# Esp32_Shield.net
KiCad netlist of a schematic drawn in EAGLE
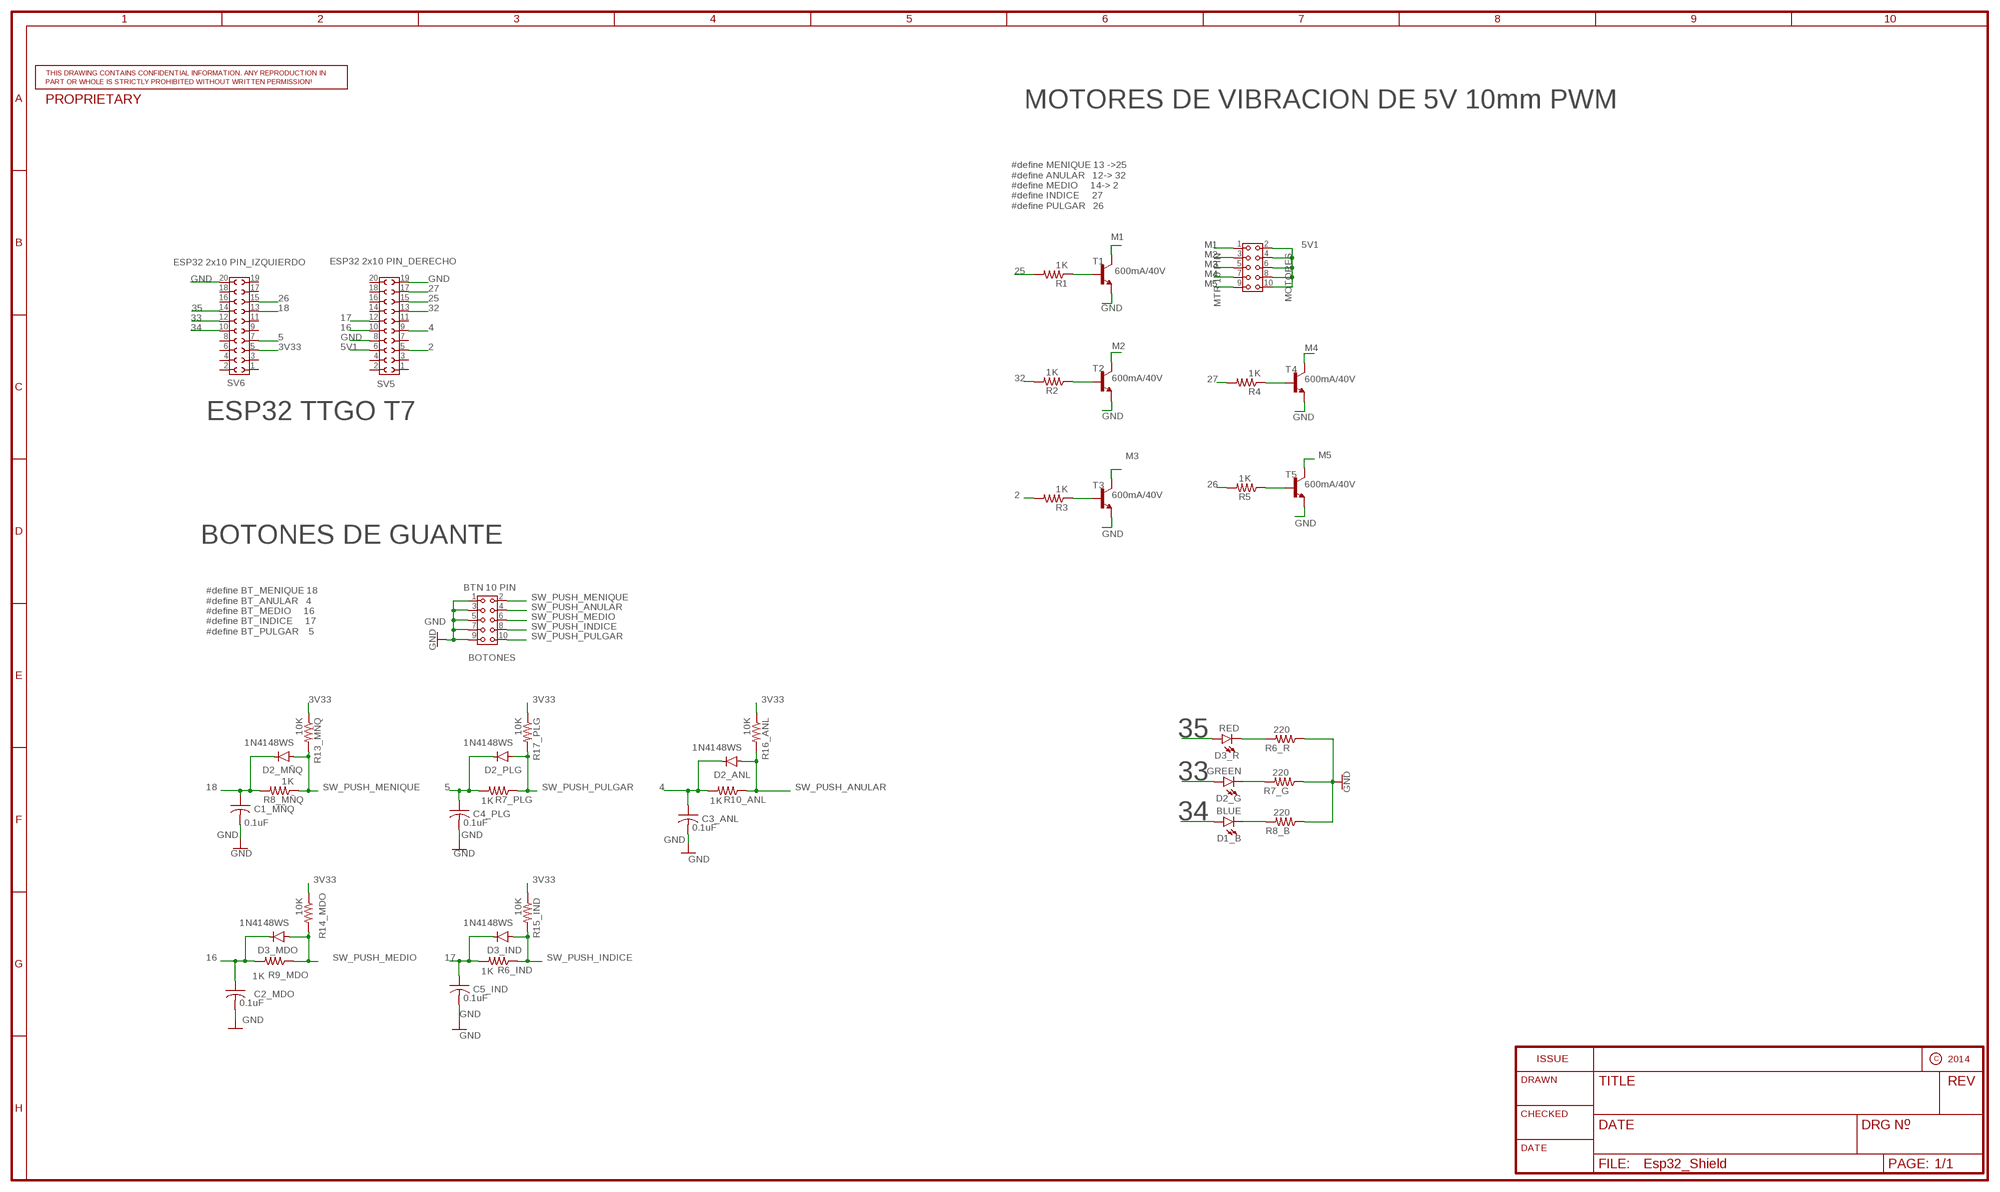
[diagram p0: schematic, sheet 1]

(export (version "E")
  (design (tool "Eeschema 10.0.6"))
  (components
    (comp (ref "BOTONES")
      (value "BTN 10 PIN")
      (footprint "eagle-import:61301021821")
      (libsource (lib "eagle-import") (part "6130XX21821_61301021821"))
    )
    (comp (ref "C1_MÑQ")
      (value "0.1uF")
      (footprint "eagle-import:C0805")
      (libsource (lib "eagle-import") (part "C-USC0805"))
    )
    (comp (ref "C2_MDO")
      (value "0.1uF")
      (footprint "eagle-import:C0805")
      (libsource (lib "eagle-import") (part "C-USC0805"))
    )
    (comp (ref "C3_ANL")
      (value "0.1uF")
      (footprint "eagle-import:C0805")
      (libsource (lib "eagle-import") (part "C-USC0805"))
    )
    (comp (ref "C4_PLG")
      (value "0.1uF")
      (footprint "eagle-import:C0805")
      (libsource (lib "eagle-import") (part "C-USC0805"))
    )
    (comp (ref "C5_IND")
      (value "0.1uF")
      (footprint "eagle-import:C0805")
      (libsource (lib "eagle-import") (part "C-USC0805"))
    )
    (comp (ref "D1_B")
      (value "BLUE")
      (footprint "eagle-import:LED-1206")
      (libsource (lib "eagle-import") (part "LED-BLUE1206"))
    )
    (comp (ref "D2_ANL")
      (value "1N4148WS")
      (footprint "eagle-import:SOD-323")
      (fields
        (field (name "DIGIKEY_PART_NUMBER") "1N4148WSFSTR-ND")
        (field (name "MANUFACTURER") "Diodes Incorporated")
        (field (name "CREATED_BY") "PCBLayout.com")
      )
      (libsource (lib "eagle-import") (part "1N4148WS"))
    )
    (comp (ref "D2_G")
      (value "GREEN")
      (footprint "eagle-import:LED-1206")
      (libsource (lib "eagle-import") (part "LED-GREEN1206"))
    )
    (comp (ref "D2_MÑQ")
      (value "1N4148WS")
      (footprint "eagle-import:SOD-323")
      (fields
        (field (name "DIGIKEY_PART_NUMBER") "1N4148WSFSTR-ND")
        (field (name "MANUFACTURER") "Diodes Incorporated")
        (field (name "CREATED_BY") "PCBLayout.com")
      )
      (libsource (lib "eagle-import") (part "1N4148WS"))
    )
    (comp (ref "D2_PLG")
      (value "1N4148WS")
      (footprint "eagle-import:SOD-323")
      (fields
        (field (name "DIGIKEY_PART_NUMBER") "1N4148WSFSTR-ND")
        (field (name "MANUFACTURER") "Diodes Incorporated")
        (field (name "CREATED_BY") "PCBLayout.com")
      )
      (libsource (lib "eagle-import") (part "1N4148WS"))
    )
    (comp (ref "D3_IND")
      (value "1N4148WS")
      (footprint "eagle-import:SOD-323")
      (fields
        (field (name "DIGIKEY_PART_NUMBER") "1N4148WSFSTR-ND")
        (field (name "MANUFACTURER") "Diodes Incorporated")
        (field (name "CREATED_BY") "PCBLayout.com")
      )
      (libsource (lib "eagle-import") (part "1N4148WS"))
    )
    (comp (ref "D3_MDO")
      (value "1N4148WS")
      (footprint "eagle-import:SOD-323")
      (fields
        (field (name "DIGIKEY_PART_NUMBER") "1N4148WSFSTR-ND")
        (field (name "MANUFACTURER") "Diodes Incorporated")
        (field (name "CREATED_BY") "PCBLayout.com")
      )
      (libsource (lib "eagle-import") (part "1N4148WS"))
    )
    (comp (ref "D3_R")
      (value "RED")
      (footprint "eagle-import:LED-1206")
      (libsource (lib "eagle-import") (part "LED-RED1206"))
    )
    (comp (ref "MOTORES")
      (value "MTR 10 PIN")
      (footprint "eagle-import:61301021821")
      (libsource (lib "eagle-import") (part "6130XX21821_61301021821"))
    )
    (comp (ref "R1")
      (value "1K")
      (footprint "eagle-import:R0805")
      (libsource (lib "eagle-import") (part "R-US_R0805"))
    )
    (comp (ref "R2")
      (value "1K")
      (footprint "eagle-import:R0805")
      (libsource (lib "eagle-import") (part "R-US_R0805"))
    )
    (comp (ref "R3")
      (value "1K")
      (footprint "eagle-import:R0805")
      (libsource (lib "eagle-import") (part "R-US_R0805"))
    )
    (comp (ref "R4")
      (value "1K")
      (footprint "eagle-import:R0805")
      (libsource (lib "eagle-import") (part "R-US_R0805"))
    )
    (comp (ref "R5")
      (value "1K")
      (footprint "eagle-import:R0805")
      (libsource (lib "eagle-import") (part "R-US_R0805"))
    )
    (comp (ref "R6_IND")
      (value "1K")
      (footprint "eagle-import:R0805")
      (libsource (lib "eagle-import") (part "R-US_R0805"))
    )
    (comp (ref "R6_R")
      (value "220")
      (footprint "eagle-import:R0805")
      (libsource (lib "eagle-import") (part "R-US_R0805"))
    )
    (comp (ref "R7_G")
      (value "220")
      (footprint "eagle-import:R0805")
      (libsource (lib "eagle-import") (part "R-US_R0805"))
    )
    (comp (ref "R7_PLG")
      (value "1K")
      (footprint "eagle-import:R0805")
      (libsource (lib "eagle-import") (part "R-US_R0805"))
    )
    (comp (ref "R8_B")
      (value "220")
      (footprint "eagle-import:R0805")
      (libsource (lib "eagle-import") (part "R-US_R0805"))
    )
    (comp (ref "R8_MÑQ")
      (value "1K")
      (footprint "eagle-import:R0805")
      (libsource (lib "eagle-import") (part "R-US_R0805"))
    )
    (comp (ref "R9_MDO")
      (value "1K")
      (footprint "eagle-import:R0805")
      (libsource (lib "eagle-import") (part "R-US_R0805"))
    )
    (comp (ref "R10_ANL")
      (value "1K")
      (footprint "eagle-import:R0805")
      (libsource (lib "eagle-import") (part "R-US_R0805"))
    )
    (comp (ref "R13_MÑQ")
      (value "10K")
      (footprint "eagle-import:R0805")
      (libsource (lib "eagle-import") (part "R-US_R0805"))
    )
    (comp (ref "R14_MDO")
      (value "10K")
      (footprint "eagle-import:R0805")
      (libsource (lib "eagle-import") (part "R-US_R0805"))
    )
    (comp (ref "R15_IND")
      (value "10K")
      (footprint "eagle-import:R0805")
      (libsource (lib "eagle-import") (part "R-US_R0805"))
    )
    (comp (ref "R16_ANL")
      (value "10K")
      (footprint "eagle-import:R0805")
      (libsource (lib "eagle-import") (part "R-US_R0805"))
    )
    (comp (ref "R17_PLG")
      (value "10K")
      (footprint "eagle-import:R0805")
      (libsource (lib "eagle-import") (part "R-US_R0805"))
    )
    (comp (ref "SV5")
      (value "ESP32 2x10 PIN_DERECHO")
      (footprint "eagle-import:61302021821")
      (libsource (lib "eagle-import") (part "6130XX21821_61302021821"))
    )
    (comp (ref "SV6")
      (value "ESP32 2x10 PIN_IZQUIERDO")
      (footprint "eagle-import:61302021821")
      (libsource (lib "eagle-import") (part "6130XX21821_61302021821"))
    )
    (comp (ref "T1")
      (value "600mA/40V")
      (footprint "eagle-import:SOT23-3")
      (libsource (lib "eagle-import") (part "TRANS_NPN-MMBT2222AL"))
    )
    (comp (ref "T2")
      (value "600mA/40V")
      (footprint "eagle-import:SOT23-3")
      (libsource (lib "eagle-import") (part "TRANS_NPN-MMBT2222AL"))
    )
    (comp (ref "T3")
      (value "600mA/40V")
      (footprint "eagle-import:SOT23-3")
      (libsource (lib "eagle-import") (part "TRANS_NPN-MMBT2222AL"))
    )
    (comp (ref "T4")
      (value "600mA/40V")
      (footprint "eagle-import:SOT23-3")
      (libsource (lib "eagle-import") (part "TRANS_NPN-MMBT2222AL"))
    )
    (comp (ref "T5")
      (value "600mA/40V")
      (footprint "eagle-import:SOT23-3")
      (libsource (lib "eagle-import") (part "TRANS_NPN-MMBT2222AL"))
    )
  )
  (nets
    (net (code "1") (name "/2") (class "Default")
      (node (ref "R3") (pin "2") (pinfunction "2_2") (pintype "passive"))
      (node (ref "SV5") (pin "5") (pinfunction "5_5") (pintype "passive"))
    )
    (net (code "2") (name "/3V33") (class "Default")
      (node (ref "R13_MÑQ") (pin "1") (pinfunction "1_1") (pintype "passive"))
      (node (ref "R14_MDO") (pin "1") (pinfunction "1_1") (pintype "passive"))
      (node (ref "R15_IND") (pin "1") (pinfunction "1_1") (pintype "passive"))
      (node (ref "R16_ANL") (pin "1") (pinfunction "1_1") (pintype "passive"))
      (node (ref "R17_PLG") (pin "1") (pinfunction "1_1") (pintype "passive"))
      (node (ref "SV6") (pin "5") (pinfunction "5_5") (pintype "passive"))
    )
    (net (code "3") (name "/4") (class "Default")
      (node (ref "C3_ANL") (pin "1") (pinfunction "1_1") (pintype "passive"))
      (node (ref "D2_ANL") (pin "C") (pinfunction "C_C") (pintype "passive"))
      (node (ref "R10_ANL") (pin "2") (pinfunction "2_2") (pintype "passive"))
      (node (ref "SV5") (pin "9") (pinfunction "9_9") (pintype "passive"))
    )
    (net (code "4") (name "/5") (class "Default")
      (node (ref "C4_PLG") (pin "1") (pinfunction "1_1") (pintype "passive"))
      (node (ref "D2_PLG") (pin "C") (pinfunction "C_C") (pintype "passive"))
      (node (ref "R7_PLG") (pin "2") (pinfunction "2_2") (pintype "passive"))
      (node (ref "SV6") (pin "7") (pinfunction "7_7") (pintype "passive"))
    )
    (net (code "5") (name "/5V1") (class "Default")
      (node (ref "MOTORES") (pin "10") (pinfunction "10_10") (pintype "passive"))
      (node (ref "MOTORES") (pin "2") (pinfunction "2_2") (pintype "passive"))
      (node (ref "MOTORES") (pin "4") (pinfunction "4_4") (pintype "passive"))
      (node (ref "MOTORES") (pin "6") (pinfunction "6_6") (pintype "passive"))
      (node (ref "MOTORES") (pin "8") (pinfunction "8_8") (pintype "passive"))
      (node (ref "SV5") (pin "6") (pinfunction "6_6") (pintype "passive"))
    )
    (net (code "6") (name "/16") (class "Default")
      (node (ref "C2_MDO") (pin "1") (pinfunction "1_1") (pintype "passive"))
      (node (ref "D3_MDO") (pin "C") (pinfunction "C_C") (pintype "passive"))
      (node (ref "R9_MDO") (pin "2") (pinfunction "2_2") (pintype "passive"))
      (node (ref "SV5") (pin "10") (pinfunction "10_10") (pintype "passive"))
    )
    (net (code "7") (name "/17") (class "Default")
      (node (ref "C5_IND") (pin "1") (pinfunction "1_1") (pintype "passive"))
      (node (ref "D3_IND") (pin "C") (pinfunction "C_C") (pintype "passive"))
      (node (ref "R6_IND") (pin "2") (pinfunction "2_2") (pintype "passive"))
      (node (ref "SV5") (pin "12") (pinfunction "12_12") (pintype "passive"))
    )
    (net (code "8") (name "/18") (class "Default")
      (node (ref "C1_MÑQ") (pin "1") (pinfunction "1_1") (pintype "passive"))
      (node (ref "D2_MÑQ") (pin "C") (pinfunction "C_C") (pintype "passive"))
      (node (ref "R8_MÑQ") (pin "2") (pinfunction "2_2") (pintype "passive"))
      (node (ref "SV6") (pin "13") (pinfunction "13_13") (pintype "passive"))
    )
    (net (code "9") (name "/25") (class "Default")
      (node (ref "R1") (pin "2") (pinfunction "2_2") (pintype "passive"))
      (node (ref "SV5") (pin "15") (pinfunction "15_15") (pintype "passive"))
    )
    (net (code "10") (name "/26") (class "Default")
      (node (ref "R5") (pin "2") (pinfunction "2_2") (pintype "passive"))
      (node (ref "SV6") (pin "15") (pinfunction "15_15") (pintype "passive"))
    )
    (net (code "11") (name "/27") (class "Default")
      (node (ref "R4") (pin "2") (pinfunction "2_2") (pintype "passive"))
      (node (ref "SV5") (pin "17") (pinfunction "17_17") (pintype "passive"))
    )
    (net (code "12") (name "/32") (class "Default")
      (node (ref "R2") (pin "2") (pinfunction "2_2") (pintype "passive"))
      (node (ref "SV5") (pin "13") (pinfunction "13_13") (pintype "passive"))
    )
    (net (code "13") (name "/33") (class "Default")
      (node (ref "D2_G") (pin "A") (pinfunction "A_A") (pintype "passive"))
      (node (ref "SV6") (pin "12") (pinfunction "12_12") (pintype "passive"))
    )
    (net (code "14") (name "/34") (class "Default")
      (node (ref "D1_B") (pin "A") (pinfunction "A_A") (pintype "passive"))
      (node (ref "SV6") (pin "10") (pinfunction "10_10") (pintype "passive"))
    )
    (net (code "15") (name "/35") (class "Default")
      (node (ref "D3_R") (pin "A") (pinfunction "A_A") (pintype "passive"))
      (node (ref "SV6") (pin "14") (pinfunction "14_14") (pintype "passive"))
    )
    (net (code "16") (name "/M1") (class "Default")
      (node (ref "MOTORES") (pin "1") (pinfunction "1_1") (pintype "passive"))
      (node (ref "T1") (pin "3") (pinfunction "C_3") (pintype "passive"))
    )
    (net (code "17") (name "/M2") (class "Default")
      (node (ref "MOTORES") (pin "3") (pinfunction "3_3") (pintype "passive"))
      (node (ref "T2") (pin "3") (pinfunction "C_3") (pintype "passive"))
    )
    (net (code "18") (name "/M3") (class "Default")
      (node (ref "MOTORES") (pin "5") (pinfunction "5_5") (pintype "passive"))
      (node (ref "T3") (pin "3") (pinfunction "C_3") (pintype "passive"))
    )
    (net (code "19") (name "/M4") (class "Default")
      (node (ref "MOTORES") (pin "7") (pinfunction "7_7") (pintype "passive"))
      (node (ref "T4") (pin "3") (pinfunction "C_3") (pintype "passive"))
    )
    (net (code "20") (name "/M5") (class "Default")
      (node (ref "MOTORES") (pin "9") (pinfunction "9_9") (pintype "passive"))
      (node (ref "T5") (pin "3") (pinfunction "C_3") (pintype "passive"))
    )
    (net (code "21") (name "/SW_PUSH_ANULAR") (class "Default")
      (node (ref "BOTONES") (pin "4") (pinfunction "4_4") (pintype "passive"))
      (node (ref "D2_ANL") (pin "A") (pinfunction "A_A") (pintype "passive"))
      (node (ref "R10_ANL") (pin "1") (pinfunction "1_1") (pintype "passive"))
      (node (ref "R16_ANL") (pin "2") (pinfunction "2_2") (pintype "passive"))
    )
    (net (code "22") (name "/SW_PUSH_INDICE") (class "Default")
      (node (ref "BOTONES") (pin "8") (pinfunction "8_8") (pintype "passive"))
      (node (ref "D3_IND") (pin "A") (pinfunction "A_A") (pintype "passive"))
      (node (ref "R15_IND") (pin "2") (pinfunction "2_2") (pintype "passive"))
      (node (ref "R6_IND") (pin "1") (pinfunction "1_1") (pintype "passive"))
    )
    (net (code "23") (name "/SW_PUSH_MEDIO") (class "Default")
      (node (ref "BOTONES") (pin "6") (pinfunction "6_6") (pintype "passive"))
      (node (ref "D3_MDO") (pin "A") (pinfunction "A_A") (pintype "passive"))
      (node (ref "R14_MDO") (pin "2") (pinfunction "2_2") (pintype "passive"))
      (node (ref "R9_MDO") (pin "1") (pinfunction "1_1") (pintype "passive"))
    )
    (net (code "24") (name "/SW_PUSH_MENIQUE") (class "Default")
      (node (ref "BOTONES") (pin "2") (pinfunction "2_2") (pintype "passive"))
      (node (ref "D2_MÑQ") (pin "A") (pinfunction "A_A") (pintype "passive"))
      (node (ref "R13_MÑQ") (pin "2") (pinfunction "2_2") (pintype "passive"))
      (node (ref "R8_MÑQ") (pin "1") (pinfunction "1_1") (pintype "passive"))
    )
    (net (code "25") (name "/SW_PUSH_PULGAR") (class "Default")
      (node (ref "BOTONES") (pin "10") (pinfunction "10_10") (pintype "passive"))
      (node (ref "D2_PLG") (pin "A") (pinfunction "A_A") (pintype "passive"))
      (node (ref "R17_PLG") (pin "2") (pinfunction "2_2") (pintype "passive"))
      (node (ref "R7_PLG") (pin "1") (pinfunction "1_1") (pintype "passive"))
    )
    (net (code "26") (name "GND") (class "Default")
      (node (ref "BOTONES") (pin "1") (pinfunction "1_1") (pintype "passive"))
      (node (ref "BOTONES") (pin "3") (pinfunction "3_3") (pintype "passive"))
      (node (ref "BOTONES") (pin "5") (pinfunction "5_5") (pintype "passive"))
      (node (ref "BOTONES") (pin "7") (pinfunction "7_7") (pintype "passive"))
      (node (ref "BOTONES") (pin "9") (pinfunction "9_9") (pintype "passive"))
      (node (ref "C1_MÑQ") (pin "2") (pinfunction "2_2") (pintype "passive"))
      (node (ref "C2_MDO") (pin "2") (pinfunction "2_2") (pintype "passive"))
      (node (ref "C3_ANL") (pin "2") (pinfunction "2_2") (pintype "passive"))
      (node (ref "C4_PLG") (pin "2") (pinfunction "2_2") (pintype "passive"))
      (node (ref "C5_IND") (pin "2") (pinfunction "2_2") (pintype "passive"))
      (node (ref "R6_R") (pin "1") (pinfunction "1_1") (pintype "passive"))
      (node (ref "R7_G") (pin "1") (pinfunction "1_1") (pintype "passive"))
      (node (ref "R8_B") (pin "1") (pinfunction "1_1") (pintype "passive"))
      (node (ref "SV5") (pin "19") (pinfunction "19_19") (pintype "passive"))
      (node (ref "SV5") (pin "8") (pinfunction "8_8") (pintype "passive"))
      (node (ref "SV6") (pin "20") (pinfunction "20_20") (pintype "passive"))
      (node (ref "T1") (pin "2") (pinfunction "E_2") (pintype "passive"))
      (node (ref "T2") (pin "2") (pinfunction "E_2") (pintype "passive"))
      (node (ref "T3") (pin "2") (pinfunction "E_2") (pintype "passive"))
      (node (ref "T4") (pin "2") (pinfunction "E_2") (pintype "passive"))
      (node (ref "T5") (pin "2") (pinfunction "E_2") (pintype "passive"))
    )
    (net (code "27") (name "Net-(D1_B-PadC)") (class "Default")
      (node (ref "D1_B") (pin "C") (pinfunction "C_C") (pintype "passive"))
      (node (ref "R8_B") (pin "2") (pinfunction "2_2") (pintype "passive"))
    )
    (net (code "28") (name "Net-(D2_G-PadC)") (class "Default")
      (node (ref "D2_G") (pin "C") (pinfunction "C_C") (pintype "passive"))
      (node (ref "R7_G") (pin "2") (pinfunction "2_2") (pintype "passive"))
    )
    (net (code "29") (name "Net-(D3_R-PadC)") (class "Default")
      (node (ref "D3_R") (pin "C") (pinfunction "C_C") (pintype "passive"))
      (node (ref "R6_R") (pin "2") (pinfunction "2_2") (pintype "passive"))
    )
    (net (code "30") (name "Net-(T1-B)") (class "Default")
      (node (ref "R1") (pin "1") (pinfunction "1_1") (pintype "passive"))
      (node (ref "T1") (pin "1") (pinfunction "B_1") (pintype "passive"))
    )
    (net (code "31") (name "Net-(T2-B)") (class "Default")
      (node (ref "R2") (pin "1") (pinfunction "1_1") (pintype "passive"))
      (node (ref "T2") (pin "1") (pinfunction "B_1") (pintype "passive"))
    )
    (net (code "32") (name "Net-(T3-B)") (class "Default")
      (node (ref "R3") (pin "1") (pinfunction "1_1") (pintype "passive"))
      (node (ref "T3") (pin "1") (pinfunction "B_1") (pintype "passive"))
    )
    (net (code "33") (name "Net-(T4-B)") (class "Default")
      (node (ref "R4") (pin "1") (pinfunction "1_1") (pintype "passive"))
      (node (ref "T4") (pin "1") (pinfunction "B_1") (pintype "passive"))
    )
    (net (code "34") (name "Net-(T5-B)") (class "Default")
      (node (ref "R5") (pin "1") (pinfunction "1_1") (pintype "passive"))
      (node (ref "T5") (pin "1") (pinfunction "B_1") (pintype "passive"))
    )
    (net (code "35") (name "unconnected-(SV5-Pad1)") (class "Default")
      (node (ref "SV5") (pin "1") (pinfunction "1_1") (pintype "passive"))
    )
    (net (code "36") (name "unconnected-(SV5-Pad2)") (class "Default")
      (node (ref "SV5") (pin "2") (pinfunction "2_2") (pintype "passive"))
    )
    (net (code "37") (name "unconnected-(SV5-Pad3)") (class "Default")
      (node (ref "SV5") (pin "3") (pinfunction "3_3") (pintype "passive"))
    )
    (net (code "38") (name "unconnected-(SV5-Pad4)") (class "Default")
      (node (ref "SV5") (pin "4") (pinfunction "4_4") (pintype "passive"))
    )
    (net (code "39") (name "unconnected-(SV5-Pad7)") (class "Default")
      (node (ref "SV5") (pin "7") (pinfunction "7_7") (pintype "passive"))
    )
    (net (code "40") (name "unconnected-(SV5-Pad11)") (class "Default")
      (node (ref "SV5") (pin "11") (pinfunction "11_11") (pintype "passive"))
    )
    (net (code "41") (name "unconnected-(SV5-Pad14)") (class "Default")
      (node (ref "SV5") (pin "14") (pinfunction "14_14") (pintype "passive"))
    )
    (net (code "42") (name "unconnected-(SV5-Pad16)") (class "Default")
      (node (ref "SV5") (pin "16") (pinfunction "16_16") (pintype "passive"))
    )
    (net (code "43") (name "unconnected-(SV5-Pad18)") (class "Default")
      (node (ref "SV5") (pin "18") (pinfunction "18_18") (pintype "passive"))
    )
    (net (code "44") (name "unconnected-(SV5-Pad20)") (class "Default")
      (node (ref "SV5") (pin "20") (pinfunction "20_20") (pintype "passive"))
    )
    (net (code "45") (name "unconnected-(SV6-Pad1)") (class "Default")
      (node (ref "SV6") (pin "1") (pinfunction "1_1") (pintype "passive"))
    )
    (net (code "46") (name "unconnected-(SV6-Pad2)") (class "Default")
      (node (ref "SV6") (pin "2") (pinfunction "2_2") (pintype "passive"))
    )
    (net (code "47") (name "unconnected-(SV6-Pad3)") (class "Default")
      (node (ref "SV6") (pin "3") (pinfunction "3_3") (pintype "passive"))
    )
    (net (code "48") (name "unconnected-(SV6-Pad4)") (class "Default")
      (node (ref "SV6") (pin "4") (pinfunction "4_4") (pintype "passive"))
    )
    (net (code "49") (name "unconnected-(SV6-Pad6)") (class "Default")
      (node (ref "SV6") (pin "6") (pinfunction "6_6") (pintype "passive"))
    )
    (net (code "50") (name "unconnected-(SV6-Pad8)") (class "Default")
      (node (ref "SV6") (pin "8") (pinfunction "8_8") (pintype "passive"))
    )
    (net (code "51") (name "unconnected-(SV6-Pad9)") (class "Default")
      (node (ref "SV6") (pin "9") (pinfunction "9_9") (pintype "passive"))
    )
    (net (code "52") (name "unconnected-(SV6-Pad11)") (class "Default")
      (node (ref "SV6") (pin "11") (pinfunction "11_11") (pintype "passive"))
    )
    (net (code "53") (name "unconnected-(SV6-Pad16)") (class "Default")
      (node (ref "SV6") (pin "16") (pinfunction "16_16") (pintype "passive"))
    )
    (net (code "54") (name "unconnected-(SV6-Pad17)") (class "Default")
      (node (ref "SV6") (pin "17") (pinfunction "17_17") (pintype "passive"))
    )
    (net (code "55") (name "unconnected-(SV6-Pad18)") (class "Default")
      (node (ref "SV6") (pin "18") (pinfunction "18_18") (pintype "passive"))
    )
    (net (code "56") (name "unconnected-(SV6-Pad19)") (class "Default")
      (node (ref "SV6") (pin "19") (pinfunction "19_19") (pintype "passive"))
    )
  )
)
